# Video_critter_mini_v01.net
KiCad netlist of a schematic drawn in EAGLE
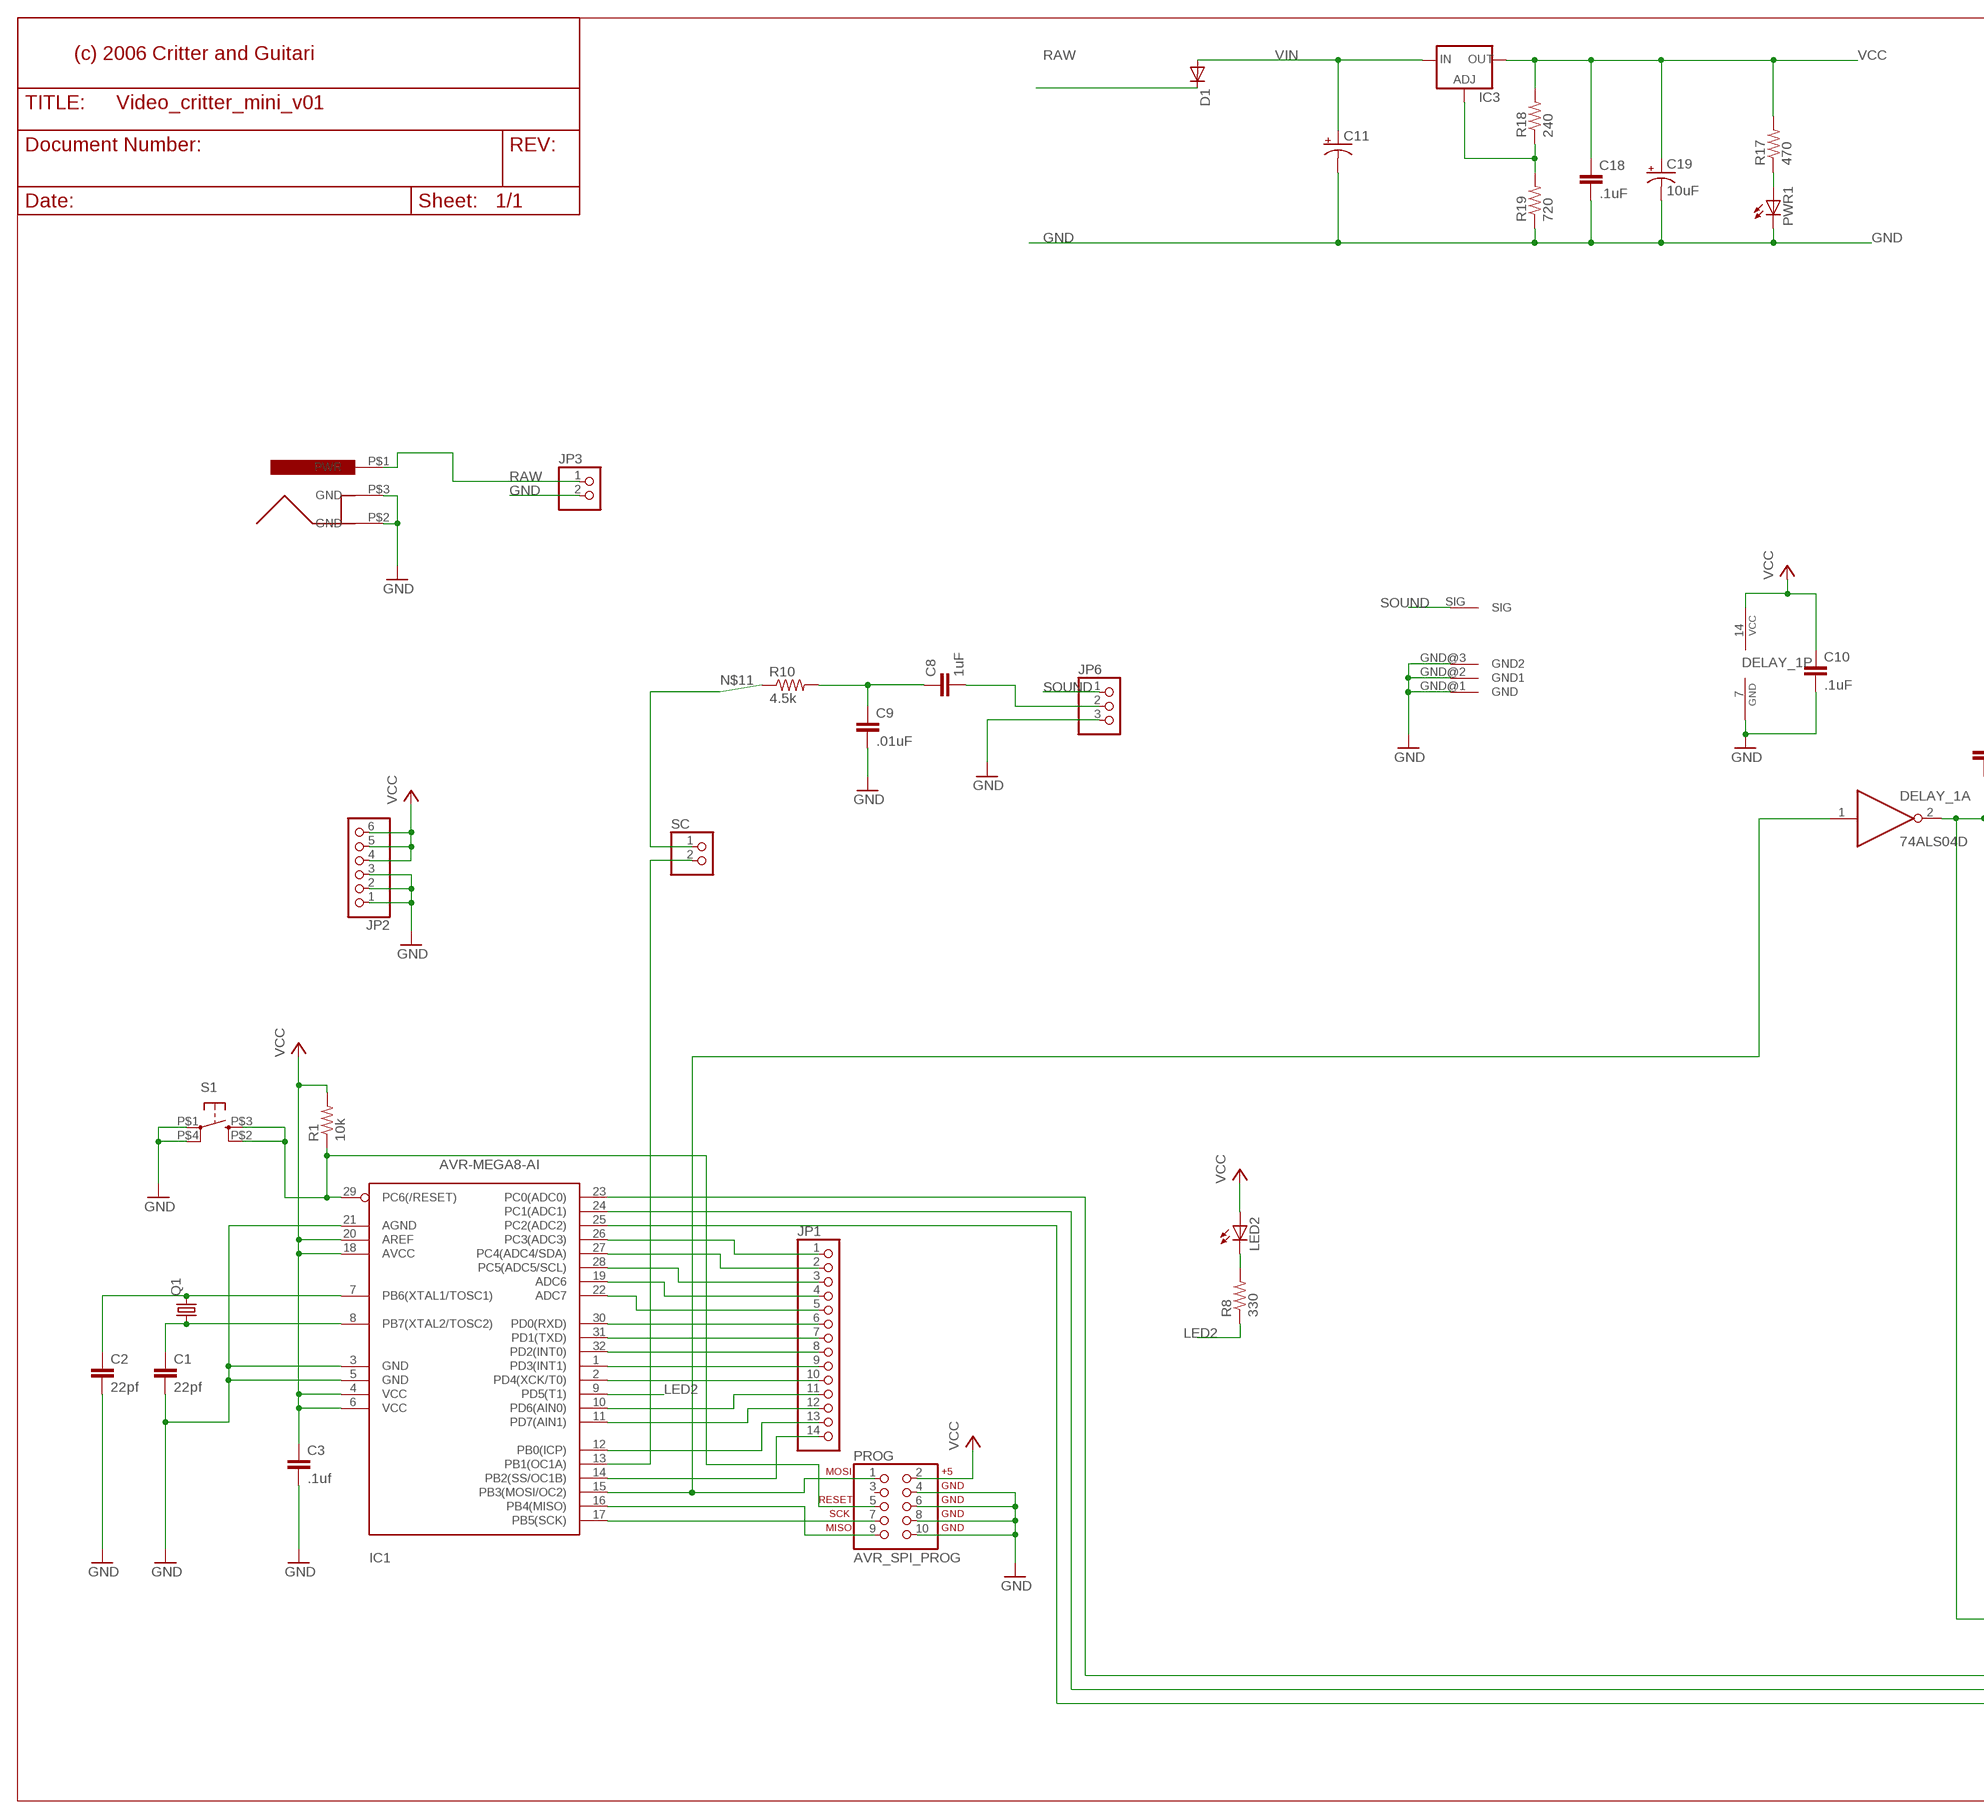
[diagram p0: schematic, sheet 1, part 1 of 2]
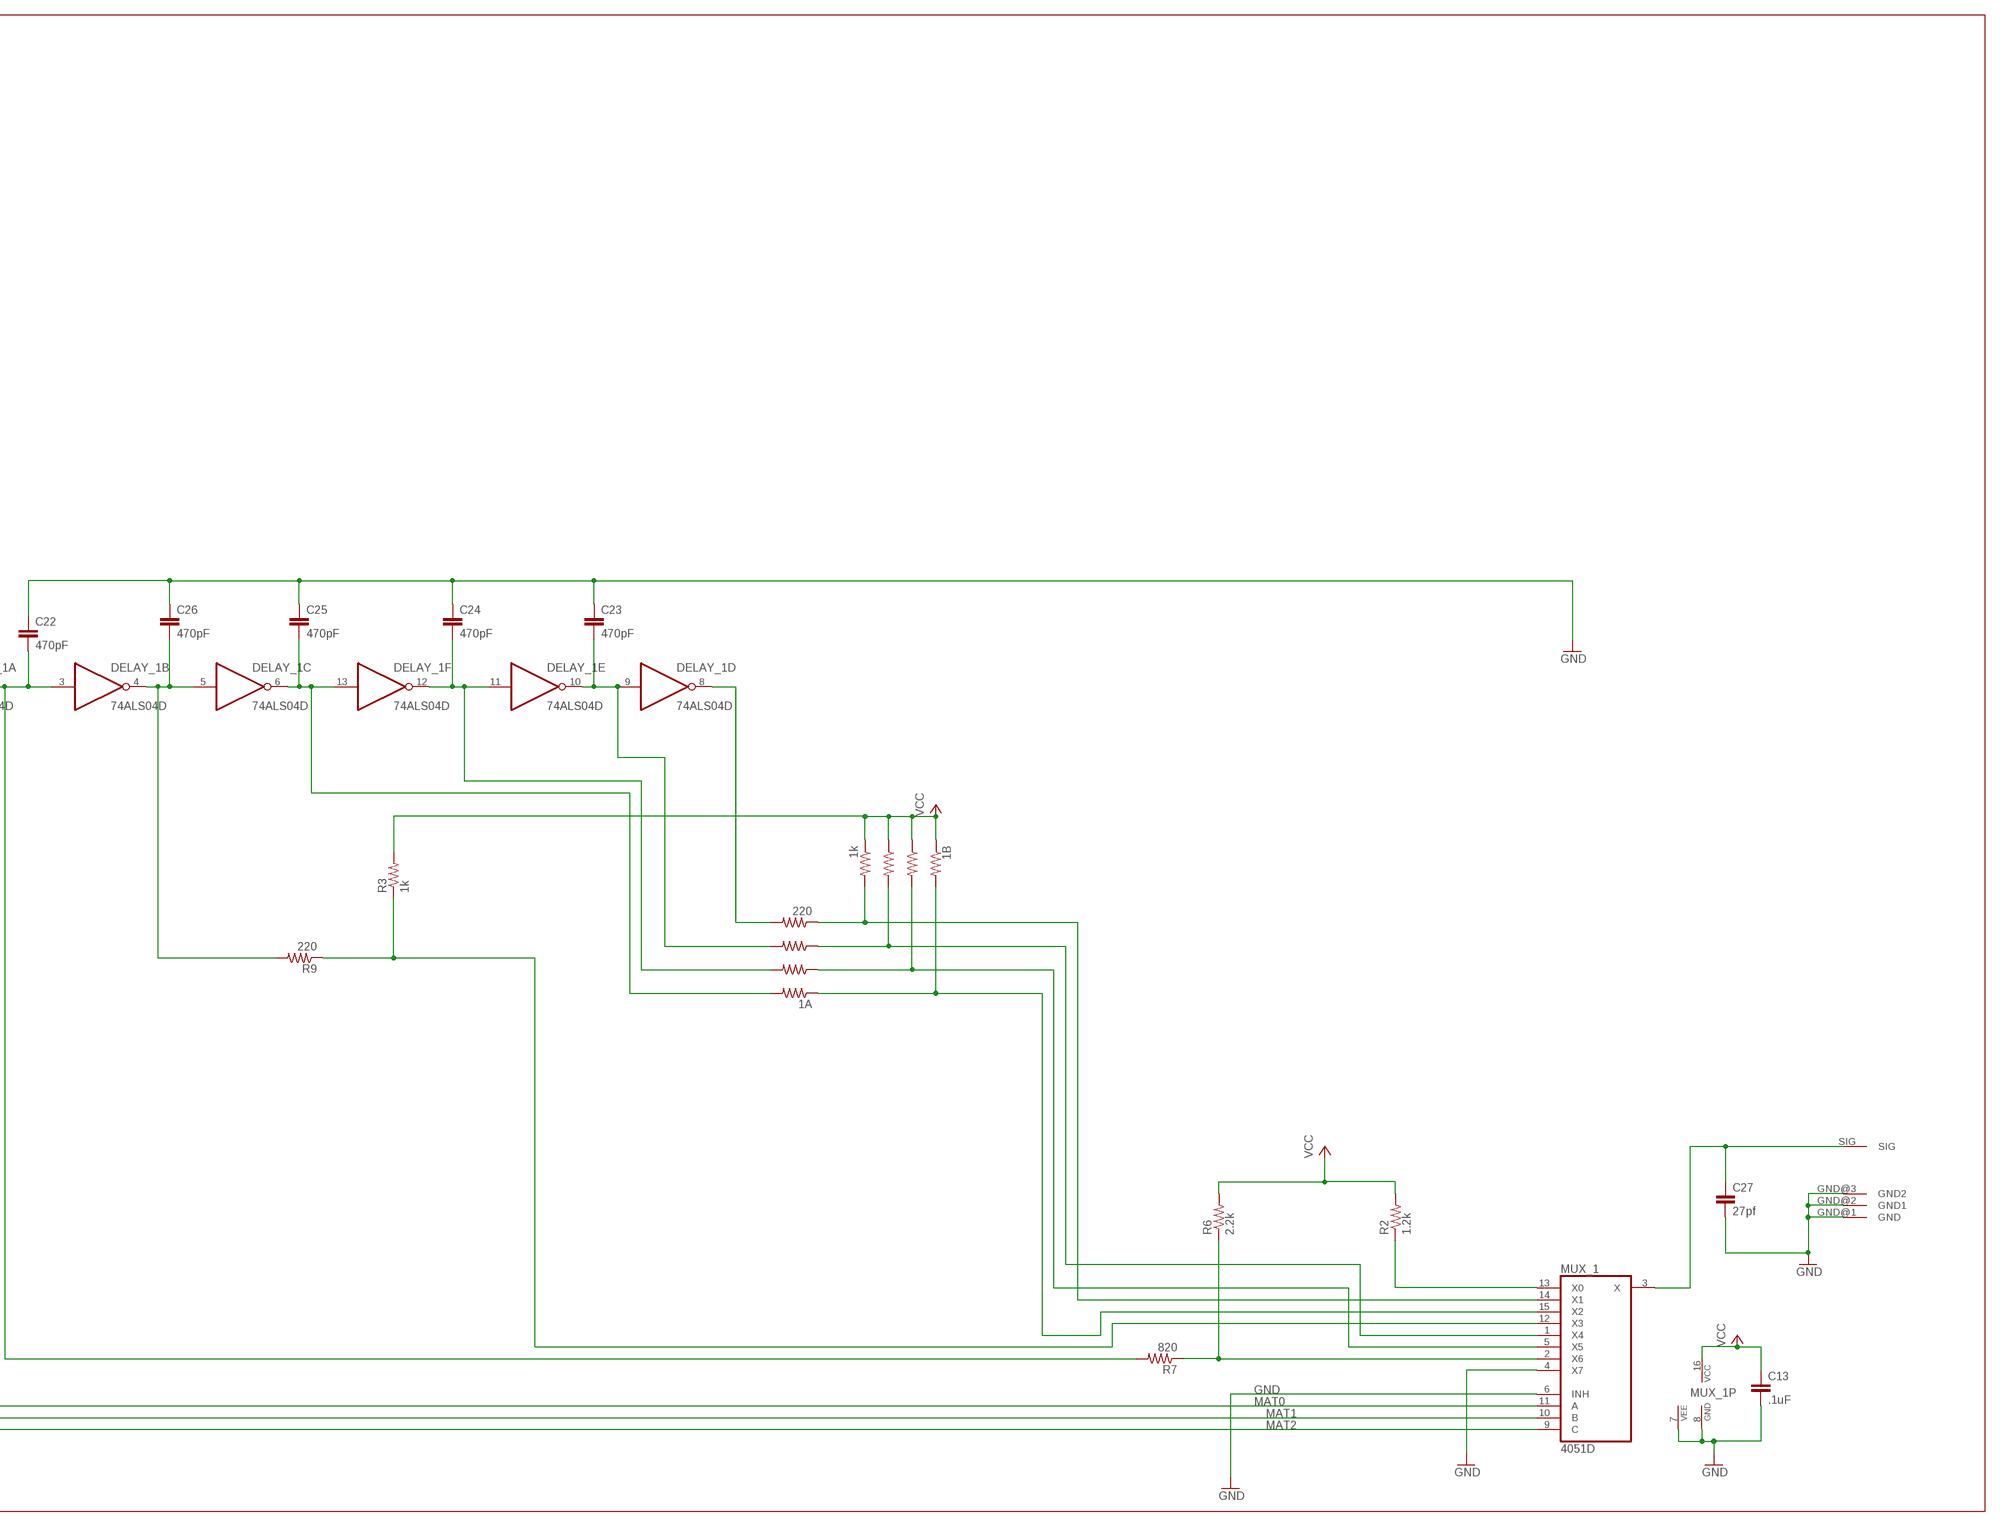
[diagram p1: schematic, sheet 1, part 2 of 2]

(export (version "E")
  (design (tool "Eeschema 10.0.6"))
  (components
    (comp (ref "1A")
      (value "220")
      (footprint "eagle-import:1206X4RESISTOR")
      (libsource (lib "eagle-import") (part "RESISTORX41206"))
    )
    (comp (ref "1B")
      (value "1k")
      (footprint "eagle-import:1206X4RESISTOR")
      (libsource (lib "eagle-import") (part "RESISTORX41206"))
    )
    (comp (ref "C1")
      (value "22pf")
      (footprint "eagle-import:C0603")
      (libsource (lib "eagle-import") (part "CAP0603"))
    )
    (comp (ref "C2")
      (value "22pf")
      (footprint "eagle-import:C0603")
      (libsource (lib "eagle-import") (part "CAP0603"))
    )
    (comp (ref "C3")
      (value ".1uf")
      (footprint "eagle-import:C0603")
      (libsource (lib "eagle-import") (part "CAP0603"))
    )
    (comp (ref "C8")
      (value "1uF")
      (footprint "eagle-import:C0603")
      (libsource (lib "eagle-import") (part "CAP0603"))
    )
    (comp (ref "C9")
      (value ".01uF")
      (footprint "eagle-import:C0603")
      (libsource (lib "eagle-import") (part "CAP0603"))
    )
    (comp (ref "C10")
      (value ".1uF")
      (footprint "eagle-import:C0603")
      (libsource (lib "eagle-import") (part "CAP0603"))
    )
    (comp (ref "C11")
      (value "CPOL-USE3.5-8")
      (footprint "eagle-import:E3,5-8")
      (libsource (lib "eagle-import") (part "CPOL-USE3.5-8"))
    )
    (comp (ref "C13")
      (value ".1uF")
      (footprint "eagle-import:C0603")
      (libsource (lib "eagle-import") (part "CAP0603"))
    )
    (comp (ref "C18")
      (value ".1uF")
      (footprint "eagle-import:C0603")
      (libsource (lib "eagle-import") (part "CAP0603"))
    )
    (comp (ref "C19")
      (value "10uF")
      (footprint "eagle-import:CPOL_1206")
      (libsource (lib "eagle-import") (part "CAP_POL1206"))
    )
    (comp (ref "C22")
      (value "470pF")
      (footprint "eagle-import:C0603")
      (libsource (lib "eagle-import") (part "CAP0603"))
    )
    (comp (ref "C23")
      (value "470pF")
      (footprint "eagle-import:C0603")
      (libsource (lib "eagle-import") (part "CAP0603"))
    )
    (comp (ref "C24")
      (value "470pF")
      (footprint "eagle-import:C0603")
      (libsource (lib "eagle-import") (part "CAP0603"))
    )
    (comp (ref "C25")
      (value "470pF")
      (footprint "eagle-import:C0603")
      (libsource (lib "eagle-import") (part "CAP0603"))
    )
    (comp (ref "C26")
      (value "470pF")
      (footprint "eagle-import:C0603")
      (libsource (lib "eagle-import") (part "CAP0603"))
    )
    (comp (ref "C27")
      (value "27pf")
      (footprint "eagle-import:C0603")
      (libsource (lib "eagle-import") (part "CAP0603"))
    )
    (comp (ref "D1")
      (value "DIODESMB")
      (footprint "eagle-import:SMB")
      (libsource (lib "eagle-import") (part "DIODESMB"))
    )
    (comp (ref "DELAY_1")
      (value "74ALS04D")
      (footprint "eagle-import:SO14")
      (libsource (lib "eagle-import") (part "7404DALS"))
    )
    (comp (ref "IC1")
      (value "AVR-MEGA8-AI")
      (footprint "eagle-import:TQFP32-08")
      (libsource (lib "eagle-import") (part "AVR-MEGA8-AI"))
    )
    (comp (ref "IC3")
      (value "V_REG_FAN1117SOT223")
      (footprint "eagle-import:SOT223")
      (libsource (lib "eagle-import") (part "V_REG_FAN1117SOT223"))
    )
    (comp (ref "JP1")
      (value "PINHD-1X14")
      (footprint "eagle-import:1X14")
      (libsource (lib "eagle-import") (part "PINHD-1X14"))
    )
    (comp (ref "JP2")
      (value "PINHD-1X6")
      (footprint "eagle-import:1X06")
      (libsource (lib "eagle-import") (part "PINHD-1X6"))
    )
    (comp (ref "JP3")
      (value "PINHD-1X2")
      (footprint "eagle-import:1X02")
      (libsource (lib "eagle-import") (part "PINHD-1X2"))
    )
    (comp (ref "JP6")
      (value "PINHD-1X3")
      (footprint "eagle-import:1X03")
      (libsource (lib "eagle-import") (part "PINHD-1X3"))
    )
    (comp (ref "LED2")
      (value "LED1206")
      (footprint "eagle-import:CHIPLED_1206")
      (libsource (lib "eagle-import") (part "LED1206"))
    )
    (comp (ref "MUX_1")
      (value "4051D")
      (footprint "eagle-import:SO16")
      (libsource (lib "eagle-import") (part "4051D"))
    )
    (comp (ref "PROG")
      (value "AVR_SPI_PROG")
      (footprint "eagle-import:PINHEAD_2X05")
      (libsource (lib "eagle-import") (part "AVR_SPI_PROG"))
    )
    (comp (ref "PWR1")
      (value "LED1206")
      (footprint "eagle-import:CHIPLED_1206")
      (libsource (lib "eagle-import") (part "LED1206"))
    )
    (comp (ref "Q1")
      (value "CRYSTALHC49UV")
      (footprint "eagle-import:HC49U-V")
      (libsource (lib "eagle-import") (part "CRYSTALHC49UV"))
    )
    (comp (ref "R1")
      (value "10k")
      (footprint "eagle-import:R0603")
      (libsource (lib "eagle-import") (part "RES0603"))
    )
    (comp (ref "R2")
      (value "1.2k")
      (footprint "eagle-import:R0603")
      (libsource (lib "eagle-import") (part "RES0603"))
    )
    (comp (ref "R3")
      (value "1k")
      (footprint "eagle-import:R0603")
      (libsource (lib "eagle-import") (part "RES0603"))
    )
    (comp (ref "R6")
      (value "2.2k")
      (footprint "eagle-import:R0603")
      (libsource (lib "eagle-import") (part "RES0603"))
    )
    (comp (ref "R7")
      (value "820")
      (footprint "eagle-import:R0603")
      (libsource (lib "eagle-import") (part "RES0603"))
    )
    (comp (ref "R8")
      (value "330")
      (footprint "eagle-import:R0603")
      (libsource (lib "eagle-import") (part "RES0603"))
    )
    (comp (ref "R9")
      (value "220")
      (footprint "eagle-import:R0603")
      (libsource (lib "eagle-import") (part "RES0603"))
    )
    (comp (ref "R10")
      (value "4.5k")
      (footprint "eagle-import:R0603")
      (libsource (lib "eagle-import") (part "RES0603"))
    )
    (comp (ref "R17")
      (value "470")
      (footprint "eagle-import:R0603")
      (libsource (lib "eagle-import") (part "RES0603"))
    )
    (comp (ref "R18")
      (value "240")
      (footprint "eagle-import:R0603")
      (libsource (lib "eagle-import") (part "RES0603"))
    )
    (comp (ref "R19")
      (value "720")
      (footprint "eagle-import:R0603")
      (libsource (lib "eagle-import") (part "RES0603"))
    )
    (comp (ref "S1")
      (value "TAC_SWITCH")
      (footprint "eagle-import:TACTILE_SWITCH_SMD")
      (libsource (lib "eagle-import") (part "TAC_SWITCH"))
    )
    (comp (ref "SC")
      (value "PINHD-1X2")
      (footprint "eagle-import:1X02")
      (libsource (lib "eagle-import") (part "PINHD-1X2"))
    )
    (comp (ref "U$1")
      (value "POWER_JACK")
      (footprint "eagle-import:POWER_JACK")
      (libsource (lib "eagle-import") (part "POWER_JACKTHRU-HOLE"))
    )
    (comp (ref "U$5")
      (value "PHONO_PLUG")
      (footprint "eagle-import:PHONO_PCB")
      (libsource (lib "eagle-import") (part "PHONO_PLUG"))
    )
    (comp (ref "U$6")
      (value "PHONO_PLUG")
      (footprint "eagle-import:PHONO_PCB")
      (libsource (lib "eagle-import") (part "PHONO_PLUG"))
    )
  )
  (nets
    (net (code "1") (name "/LED2") (class "Default")
      (node (ref "IC1") (pin "9") (pinfunction "PD5(T1)_9") (pintype "bidirectional"))
      (node (ref "R8") (pin "1") (pinfunction "1_1") (pintype "passive"))
    )
    (net (code "2") (name "/MAT0") (class "Default")
      (node (ref "IC1") (pin "23") (pinfunction "PC0(ADC0)_23") (pintype "bidirectional"))
      (node (ref "MUX_1") (pin "11") (pinfunction "A_11") (pintype "input"))
    )
    (net (code "3") (name "/MAT1") (class "Default")
      (node (ref "IC1") (pin "24") (pinfunction "PC1(ADC1)_24") (pintype "bidirectional"))
      (node (ref "MUX_1") (pin "10") (pinfunction "B_10") (pintype "input"))
    )
    (net (code "4") (name "/MAT2") (class "Default")
      (node (ref "IC1") (pin "25") (pinfunction "PC2(ADC2)_25") (pintype "bidirectional"))
      (node (ref "MUX_1") (pin "9") (pinfunction "C_9") (pintype "input"))
    )
    (net (code "5") (name "/N$11") (class "Default")
      (node (ref "R10") (pin "1") (pinfunction "1_1") (pintype "passive"))
      (node (ref "SC") (pin "1") (pinfunction "1_1") (pintype "passive"))
    )
    (net (code "6") (name "/RAW") (class "Default")
      (node (ref "D1") (pin "1") (pinfunction "C_1") (pintype "passive"))
      (node (ref "JP3") (pin "1") (pinfunction "1_1") (pintype "passive"))
      (node (ref "U$1") (pin "P$1") (pinfunction "PWR_P$1") (pintype "bidirectional"))
    )
    (net (code "7") (name "/SOUND") (class "Default")
      (node (ref "JP6") (pin "1") (pinfunction "1_1") (pintype "passive"))
      (node (ref "U$5") (pin "SIG") (pinfunction "SIG_SIG") (pintype "bidirectional"))
    )
    (net (code "8") (name "/VIN") (class "Default")
      (node (ref "C11") (pin "+") (pinfunction "+_+") (pintype "passive"))
      (node (ref "D1") (pin "2") (pinfunction "A_2") (pintype "passive"))
      (node (ref "IC3") (pin "3") (pinfunction "IN_3") (pintype "input"))
    )
    (net (code "9") (name "GND") (class "Default")
      (node (ref "C1") (pin "2") (pinfunction "2_2") (pintype "passive"))
      (node (ref "C10") (pin "2") (pinfunction "2_2") (pintype "passive"))
      (node (ref "C11") (pin "-") (pinfunction "-_-") (pintype "passive"))
      (node (ref "C13") (pin "2") (pinfunction "2_2") (pintype "passive"))
      (node (ref "C18") (pin "2") (pinfunction "2_2") (pintype "passive"))
      (node (ref "C19") (pin "C") (pinfunction "-_C") (pintype "passive"))
      (node (ref "C2") (pin "2") (pinfunction "2_2") (pintype "passive"))
      (node (ref "C22") (pin "1") (pinfunction "1_1") (pintype "passive"))
      (node (ref "C23") (pin "1") (pinfunction "1_1") (pintype "passive"))
      (node (ref "C24") (pin "1") (pinfunction "1_1") (pintype "passive"))
      (node (ref "C25") (pin "1") (pinfunction "1_1") (pintype "passive"))
      (node (ref "C26") (pin "1") (pinfunction "1_1") (pintype "passive"))
      (node (ref "C27") (pin "2") (pinfunction "2_2") (pintype "passive"))
      (node (ref "C3") (pin "2") (pinfunction "2_2") (pintype "passive"))
      (node (ref "C9") (pin "2") (pinfunction "2_2") (pintype "passive"))
      (node (ref "DELAY_1") (pin "7") (pinfunction "GND_7") (pintype "power_in"))
      (node (ref "IC1") (pin "21") (pinfunction "AGND_21") (pintype "bidirectional"))
      (node (ref "IC1") (pin "3") (pinfunction "GND_3") (pintype "bidirectional"))
      (node (ref "IC1") (pin "5") (pinfunction "GND_5") (pintype "bidirectional"))
      (node (ref "JP2") (pin "1") (pinfunction "1_1") (pintype "passive"))
      (node (ref "JP2") (pin "2") (pinfunction "2_2") (pintype "passive"))
      (node (ref "JP2") (pin "3") (pinfunction "3_3") (pintype "passive"))
      (node (ref "JP3") (pin "2") (pinfunction "2_2") (pintype "passive"))
      (node (ref "JP6") (pin "3") (pinfunction "3_3") (pintype "passive"))
      (node (ref "MUX_1") (pin "4") (pinfunction "X7_4") (pintype "bidirectional"))
      (node (ref "MUX_1") (pin "6") (pinfunction "INH_6") (pintype "input"))
      (node (ref "MUX_1") (pin "7") (pinfunction "VEE_7") (pintype "power_in"))
      (node (ref "MUX_1") (pin "8") (pinfunction "GND_8") (pintype "power_in"))
      (node (ref "PROG") (pin "10") (pinfunction "10_10") (pintype "passive"))
      (node (ref "PROG") (pin "4") (pinfunction "4_4") (pintype "passive"))
      (node (ref "PROG") (pin "6") (pinfunction "6_6") (pintype "passive"))
      (node (ref "PROG") (pin "8") (pinfunction "8_8") (pintype "passive"))
      (node (ref "PWR1") (pin "C") (pinfunction "C_C") (pintype "passive"))
      (node (ref "R19") (pin "1") (pinfunction "1_1") (pintype "passive"))
      (node (ref "S1") (pin "P$1") (pinfunction "P_P$1") (pintype "passive"))
      (node (ref "S1") (pin "P$4") (pinfunction "P1_P$4") (pintype "passive"))
      (node (ref "U$1") (pin "P$2") (pinfunction "GND_P$2") (pintype "bidirectional"))
      (node (ref "U$1") (pin "P$3") (pinfunction "GND_P$3") (pintype "bidirectional"))
      (node (ref "U$5") (pin "GND@1") (pinfunction "GND_GND@1") (pintype "bidirectional"))
      (node (ref "U$5") (pin "GND@2") (pinfunction "GND1_GND@2") (pintype "bidirectional"))
      (node (ref "U$5") (pin "GND@3") (pinfunction "GND2_GND@3") (pintype "bidirectional"))
      (node (ref "U$6") (pin "GND@1") (pinfunction "GND_GND@1") (pintype "bidirectional"))
      (node (ref "U$6") (pin "GND@2") (pinfunction "GND1_GND@2") (pintype "bidirectional"))
      (node (ref "U$6") (pin "GND@3") (pinfunction "GND2_GND@3") (pintype "bidirectional"))
    )
    (net (code "10") (name "Net-(1A-1)") (class "Default")
      (node (ref "1A") (pin "P$3") (pinfunction "1_P$3") (pintype "passive"))
      (node (ref "1B") (pin "P$4") (pinfunction "2_P$4") (pintype "passive"))
      (node (ref "MUX_1") (pin "1") (pinfunction "X4_1") (pintype "bidirectional"))
    )
    (net (code "11") (name "Net-(1A-2)") (class "Default")
      (node (ref "1A") (pin "P$4") (pinfunction "2_P$4") (pintype "passive"))
      (node (ref "C23") (pin "2") (pinfunction "2_2") (pintype "passive"))
      (node (ref "DELAY_1") (pin "10") (pinfunction "O_10") (pintype "output"))
      (node (ref "DELAY_1") (pin "9") (pinfunction "I_9") (pintype "input"))
    )
    (net (code "12") (name "Net-(1A-3)") (class "Default")
      (node (ref "1A") (pin "P$6") (pinfunction "3_P$6") (pintype "passive"))
      (node (ref "C24") (pin "2") (pinfunction "2_2") (pintype "passive"))
      (node (ref "DELAY_1") (pin "11") (pinfunction "I_11") (pintype "input"))
      (node (ref "DELAY_1") (pin "12") (pinfunction "O_12") (pintype "output"))
    )
    (net (code "13") (name "Net-(1A-4)") (class "Default")
      (node (ref "1A") (pin "P$5") (pinfunction "4_P$5") (pintype "passive"))
      (node (ref "1B") (pin "P$6") (pinfunction "3_P$6") (pintype "passive"))
      (node (ref "MUX_1") (pin "5") (pinfunction "X5_5") (pintype "bidirectional"))
    )
    (net (code "14") (name "Net-(1A-5)") (class "Default")
      (node (ref "1A") (pin "P$2") (pinfunction "5_P$2") (pintype "passive"))
      (node (ref "DELAY_1") (pin "8") (pinfunction "O_8") (pintype "output"))
    )
    (net (code "15") (name "Net-(1A-6)") (class "Default")
      (node (ref "1A") (pin "P$1") (pinfunction "6_P$1") (pintype "passive"))
      (node (ref "1B") (pin "P$2") (pinfunction "5_P$2") (pintype "passive"))
      (node (ref "MUX_1") (pin "14") (pinfunction "X1_14") (pintype "bidirectional"))
    )
    (net (code "16") (name "Net-(1A-7)") (class "Default")
      (node (ref "1A") (pin "P$8") (pinfunction "7_P$8") (pintype "passive"))
      (node (ref "C25") (pin "2") (pinfunction "2_2") (pintype "passive"))
      (node (ref "DELAY_1") (pin "13") (pinfunction "I_13") (pintype "input"))
      (node (ref "DELAY_1") (pin "6") (pinfunction "O_6") (pintype "output"))
    )
    (net (code "17") (name "Net-(1A-8)") (class "Default")
      (node (ref "1A") (pin "P$7") (pinfunction "8_P$7") (pintype "passive"))
      (node (ref "1B") (pin "P$8") (pinfunction "7_P$8") (pintype "passive"))
      (node (ref "MUX_1") (pin "15") (pinfunction "X2_15") (pintype "bidirectional"))
    )
    (net (code "18") (name "Net-(C8-Pad1)") (class "Default")
      (node (ref "C8") (pin "1") (pinfunction "1_1") (pintype "passive"))
      (node (ref "C9") (pin "1") (pinfunction "1_1") (pintype "passive"))
      (node (ref "R10") (pin "2") (pinfunction "2_2") (pintype "passive"))
    )
    (net (code "19") (name "Net-(C8-Pad2)") (class "Default")
      (node (ref "C8") (pin "2") (pinfunction "2_2") (pintype "passive"))
      (node (ref "JP6") (pin "2") (pinfunction "2_2") (pintype "passive"))
    )
    (net (code "20") (name "Net-(DELAY_1A-I)") (class "Default")
      (node (ref "DELAY_1") (pin "1") (pinfunction "I_1") (pintype "input"))
      (node (ref "IC1") (pin "15") (pinfunction "PB3(MOSI/OC2)_15") (pintype "bidirectional"))
      (node (ref "PROG") (pin "1") (pinfunction "1_1") (pintype "passive"))
    )
    (net (code "21") (name "Net-(DELAY_1A-O)") (class "Default")
      (node (ref "C22") (pin "2") (pinfunction "2_2") (pintype "passive"))
      (node (ref "DELAY_1") (pin "2") (pinfunction "O_2") (pintype "output"))
      (node (ref "DELAY_1") (pin "3") (pinfunction "I_3") (pintype "input"))
      (node (ref "R7") (pin "2") (pinfunction "2_2") (pintype "passive"))
    )
    (net (code "22") (name "Net-(DELAY_1B-O)") (class "Default")
      (node (ref "C26") (pin "2") (pinfunction "2_2") (pintype "passive"))
      (node (ref "DELAY_1") (pin "4") (pinfunction "O_4") (pintype "output"))
      (node (ref "DELAY_1") (pin "5") (pinfunction "I_5") (pintype "input"))
      (node (ref "R9") (pin "2") (pinfunction "2_2") (pintype "passive"))
    )
    (net (code "23") (name "Net-(IC1-ADC6)") (class "Default")
      (node (ref "IC1") (pin "19") (pinfunction "ADC6_19") (pintype "bidirectional"))
      (node (ref "JP1") (pin "4") (pinfunction "4_4") (pintype "passive"))
    )
    (net (code "24") (name "Net-(IC1-ADC7)") (class "Default")
      (node (ref "IC1") (pin "22") (pinfunction "ADC7_22") (pintype "bidirectional"))
      (node (ref "JP1") (pin "5") (pinfunction "5_5") (pintype "passive"))
    )
    (net (code "25") (name "Net-(IC1-PB0(ICP))") (class "Default")
      (node (ref "IC1") (pin "12") (pinfunction "PB0(ICP)_12") (pintype "bidirectional"))
      (node (ref "JP1") (pin "13") (pinfunction "13_13") (pintype "passive"))
    )
    (net (code "26") (name "Net-(IC1-PB1(OC1A))") (class "Default")
      (node (ref "IC1") (pin "13") (pinfunction "PB1(OC1A)_13") (pintype "bidirectional"))
      (node (ref "SC") (pin "2") (pinfunction "2_2") (pintype "passive"))
    )
    (net (code "27") (name "Net-(IC1-PB2(SS{slash}OC1B))") (class "Default")
      (node (ref "IC1") (pin "14") (pinfunction "PB2(SS/OC1B)_14") (pintype "bidirectional"))
      (node (ref "JP1") (pin "14") (pinfunction "14_14") (pintype "passive"))
    )
    (net (code "28") (name "Net-(IC1-PB4(MISO))") (class "Default")
      (node (ref "IC1") (pin "16") (pinfunction "PB4(MISO)_16") (pintype "bidirectional"))
      (node (ref "PROG") (pin "9") (pinfunction "9_9") (pintype "passive"))
    )
    (net (code "29") (name "Net-(IC1-PB5(SCK))") (class "Default")
      (node (ref "IC1") (pin "17") (pinfunction "PB5(SCK)_17") (pintype "bidirectional"))
      (node (ref "PROG") (pin "7") (pinfunction "7_7") (pintype "passive"))
    )
    (net (code "30") (name "Net-(IC1-PB6(XTAL1{slash}TOSC1))") (class "Default")
      (node (ref "C2") (pin "1") (pinfunction "1_1") (pintype "passive"))
      (node (ref "IC1") (pin "7") (pinfunction "PB6(XTAL1/TOSC1)_7") (pintype "bidirectional"))
      (node (ref "Q1") (pin "2") (pinfunction "2_2") (pintype "passive"))
    )
    (net (code "31") (name "Net-(IC1-PB7(XTAL2{slash}TOSC2))") (class "Default")
      (node (ref "C1") (pin "1") (pinfunction "1_1") (pintype "passive"))
      (node (ref "IC1") (pin "8") (pinfunction "PB7(XTAL2/TOSC2)_8") (pintype "bidirectional"))
      (node (ref "Q1") (pin "1") (pinfunction "1_1") (pintype "passive"))
    )
    (net (code "32") (name "Net-(IC1-PC3(ADC3))") (class "Default")
      (node (ref "IC1") (pin "26") (pinfunction "PC3(ADC3)_26") (pintype "bidirectional"))
      (node (ref "JP1") (pin "1") (pinfunction "1_1") (pintype "passive"))
    )
    (net (code "33") (name "Net-(IC1-PC4(ADC4{slash}SDA))") (class "Default")
      (node (ref "IC1") (pin "27") (pinfunction "PC4(ADC4/SDA)_27") (pintype "bidirectional"))
      (node (ref "JP1") (pin "2") (pinfunction "2_2") (pintype "passive"))
    )
    (net (code "34") (name "Net-(IC1-PC5(ADC5{slash}SCL))") (class "Default")
      (node (ref "IC1") (pin "28") (pinfunction "PC5(ADC5/SCL)_28") (pintype "bidirectional"))
      (node (ref "JP1") (pin "3") (pinfunction "3_3") (pintype "passive"))
    )
    (net (code "35") (name "Net-(IC1-PC6({slash}RESET))") (class "Default")
      (node (ref "IC1") (pin "29") (pinfunction "PC6(/RESET)_29") (pintype "bidirectional"))
      (node (ref "PROG") (pin "5") (pinfunction "5_5") (pintype "passive"))
      (node (ref "R1") (pin "1") (pinfunction "1_1") (pintype "passive"))
      (node (ref "S1") (pin "P$2") (pinfunction "S1_P$2") (pintype "passive"))
      (node (ref "S1") (pin "P$3") (pinfunction "S_P$3") (pintype "passive"))
    )
    (net (code "36") (name "Net-(IC1-PD0(RXD))") (class "Default")
      (node (ref "IC1") (pin "30") (pinfunction "PD0(RXD)_30") (pintype "bidirectional"))
      (node (ref "JP1") (pin "6") (pinfunction "6_6") (pintype "passive"))
    )
    (net (code "37") (name "Net-(IC1-PD1(TXD))") (class "Default")
      (node (ref "IC1") (pin "31") (pinfunction "PD1(TXD)_31") (pintype "bidirectional"))
      (node (ref "JP1") (pin "7") (pinfunction "7_7") (pintype "passive"))
    )
    (net (code "38") (name "Net-(IC1-PD2(INT0))") (class "Default")
      (node (ref "IC1") (pin "32") (pinfunction "PD2(INT0)_32") (pintype "bidirectional"))
      (node (ref "JP1") (pin "8") (pinfunction "8_8") (pintype "passive"))
    )
    (net (code "39") (name "Net-(IC1-PD3(INT1))") (class "Default")
      (node (ref "IC1") (pin "1") (pinfunction "PD3(INT1)_1") (pintype "bidirectional"))
      (node (ref "JP1") (pin "9") (pinfunction "9_9") (pintype "passive"))
    )
    (net (code "40") (name "Net-(IC1-PD4(XCK{slash}T0))") (class "Default")
      (node (ref "IC1") (pin "2") (pinfunction "PD4(XCK/T0)_2") (pintype "bidirectional"))
      (node (ref "JP1") (pin "10") (pinfunction "10_10") (pintype "passive"))
    )
    (net (code "41") (name "Net-(IC1-PD6(AIN0))") (class "Default")
      (node (ref "IC1") (pin "10") (pinfunction "PD6(AIN0)_10") (pintype "bidirectional"))
      (node (ref "JP1") (pin "11") (pinfunction "11_11") (pintype "passive"))
    )
    (net (code "42") (name "Net-(IC1-PD7(AIN1))") (class "Default")
      (node (ref "IC1") (pin "11") (pinfunction "PD7(AIN1)_11") (pintype "bidirectional"))
      (node (ref "JP1") (pin "12") (pinfunction "12_12") (pintype "passive"))
    )
    (net (code "43") (name "Net-(IC3-ADJ)") (class "Default")
      (node (ref "IC3") (pin "1") (pinfunction "ADJ_1") (pintype "input"))
      (node (ref "R18") (pin "1") (pinfunction "1_1") (pintype "passive"))
      (node (ref "R19") (pin "2") (pinfunction "2_2") (pintype "passive"))
    )
    (net (code "44") (name "Net-(LED2-PadC)") (class "Default")
      (node (ref "LED2") (pin "C") (pinfunction "C_C") (pintype "passive"))
      (node (ref "R8") (pin "2") (pinfunction "2_2") (pintype "passive"))
    )
    (net (code "45") (name "Net-(MUX_1A-X)") (class "Default")
      (node (ref "C27") (pin "1") (pinfunction "1_1") (pintype "passive"))
      (node (ref "MUX_1") (pin "3") (pinfunction "X_3") (pintype "bidirectional"))
      (node (ref "U$6") (pin "SIG") (pinfunction "SIG_SIG") (pintype "bidirectional"))
    )
    (net (code "46") (name "Net-(MUX_1A-X0)") (class "Default")
      (node (ref "MUX_1") (pin "13") (pinfunction "X0_13") (pintype "bidirectional"))
      (node (ref "R2") (pin "1") (pinfunction "1_1") (pintype "passive"))
    )
    (net (code "47") (name "Net-(MUX_1A-X3)") (class "Default")
      (node (ref "MUX_1") (pin "12") (pinfunction "X3_12") (pintype "bidirectional"))
      (node (ref "R3") (pin "1") (pinfunction "1_1") (pintype "passive"))
      (node (ref "R9") (pin "1") (pinfunction "1_1") (pintype "passive"))
    )
    (net (code "48") (name "Net-(MUX_1A-X6)") (class "Default")
      (node (ref "MUX_1") (pin "2") (pinfunction "X6_2") (pintype "bidirectional"))
      (node (ref "R6") (pin "1") (pinfunction "1_1") (pintype "passive"))
      (node (ref "R7") (pin "1") (pinfunction "1_1") (pintype "passive"))
    )
    (net (code "49") (name "Net-(PWR1-PadA)") (class "Default")
      (node (ref "PWR1") (pin "A") (pinfunction "A_A") (pintype "passive"))
      (node (ref "R17") (pin "1") (pinfunction "1_1") (pintype "passive"))
    )
    (net (code "50") (name "VCC") (class "Default")
      (node (ref "1B") (pin "P$1") (pinfunction "6_P$1") (pintype "passive"))
      (node (ref "1B") (pin "P$3") (pinfunction "1_P$3") (pintype "passive"))
      (node (ref "1B") (pin "P$5") (pinfunction "4_P$5") (pintype "passive"))
      (node (ref "1B") (pin "P$7") (pinfunction "8_P$7") (pintype "passive"))
      (node (ref "C10") (pin "1") (pinfunction "1_1") (pintype "passive"))
      (node (ref "C13") (pin "1") (pinfunction "1_1") (pintype "passive"))
      (node (ref "C18") (pin "1") (pinfunction "1_1") (pintype "passive"))
      (node (ref "C19") (pin "A") (pinfunction "+_A") (pintype "passive"))
      (node (ref "C3") (pin "1") (pinfunction "1_1") (pintype "passive"))
      (node (ref "DELAY_1") (pin "14") (pinfunction "VCC_14") (pintype "power_in"))
      (node (ref "IC1") (pin "18") (pinfunction "AVCC_18") (pintype "bidirectional"))
      (node (ref "IC1") (pin "20") (pinfunction "AREF_20") (pintype "bidirectional"))
      (node (ref "IC1") (pin "4") (pinfunction "VCC_4") (pintype "bidirectional"))
      (node (ref "IC1") (pin "6") (pinfunction "VCC_6") (pintype "bidirectional"))
      (node (ref "IC3") (pin "2") (pinfunction "OUT_2") (pintype "passive"))
      (node (ref "JP2") (pin "4") (pinfunction "4_4") (pintype "passive"))
      (node (ref "JP2") (pin "5") (pinfunction "5_5") (pintype "passive"))
      (node (ref "JP2") (pin "6") (pinfunction "6_6") (pintype "passive"))
      (node (ref "LED2") (pin "A") (pinfunction "A_A") (pintype "passive"))
      (node (ref "MUX_1") (pin "16") (pinfunction "VCC_16") (pintype "power_in"))
      (node (ref "PROG") (pin "2") (pinfunction "2_2") (pintype "passive"))
      (node (ref "R1") (pin "2") (pinfunction "2_2") (pintype "passive"))
      (node (ref "R17") (pin "2") (pinfunction "2_2") (pintype "passive"))
      (node (ref "R18") (pin "2") (pinfunction "2_2") (pintype "passive"))
      (node (ref "R2") (pin "2") (pinfunction "2_2") (pintype "passive"))
      (node (ref "R3") (pin "2") (pinfunction "2_2") (pintype "passive"))
      (node (ref "R6") (pin "2") (pinfunction "2_2") (pintype "passive"))
    )
    (net (code "51") (name "unconnected-(PROG-Pad3)") (class "Default")
      (node (ref "PROG") (pin "3") (pinfunction "3_3") (pintype "passive"))
    )
  )
)
